# SCH_Trabalho-AP1-Subtrator_2024-10-15.net
KiCad netlist of a schematic drawn in EasyEDA
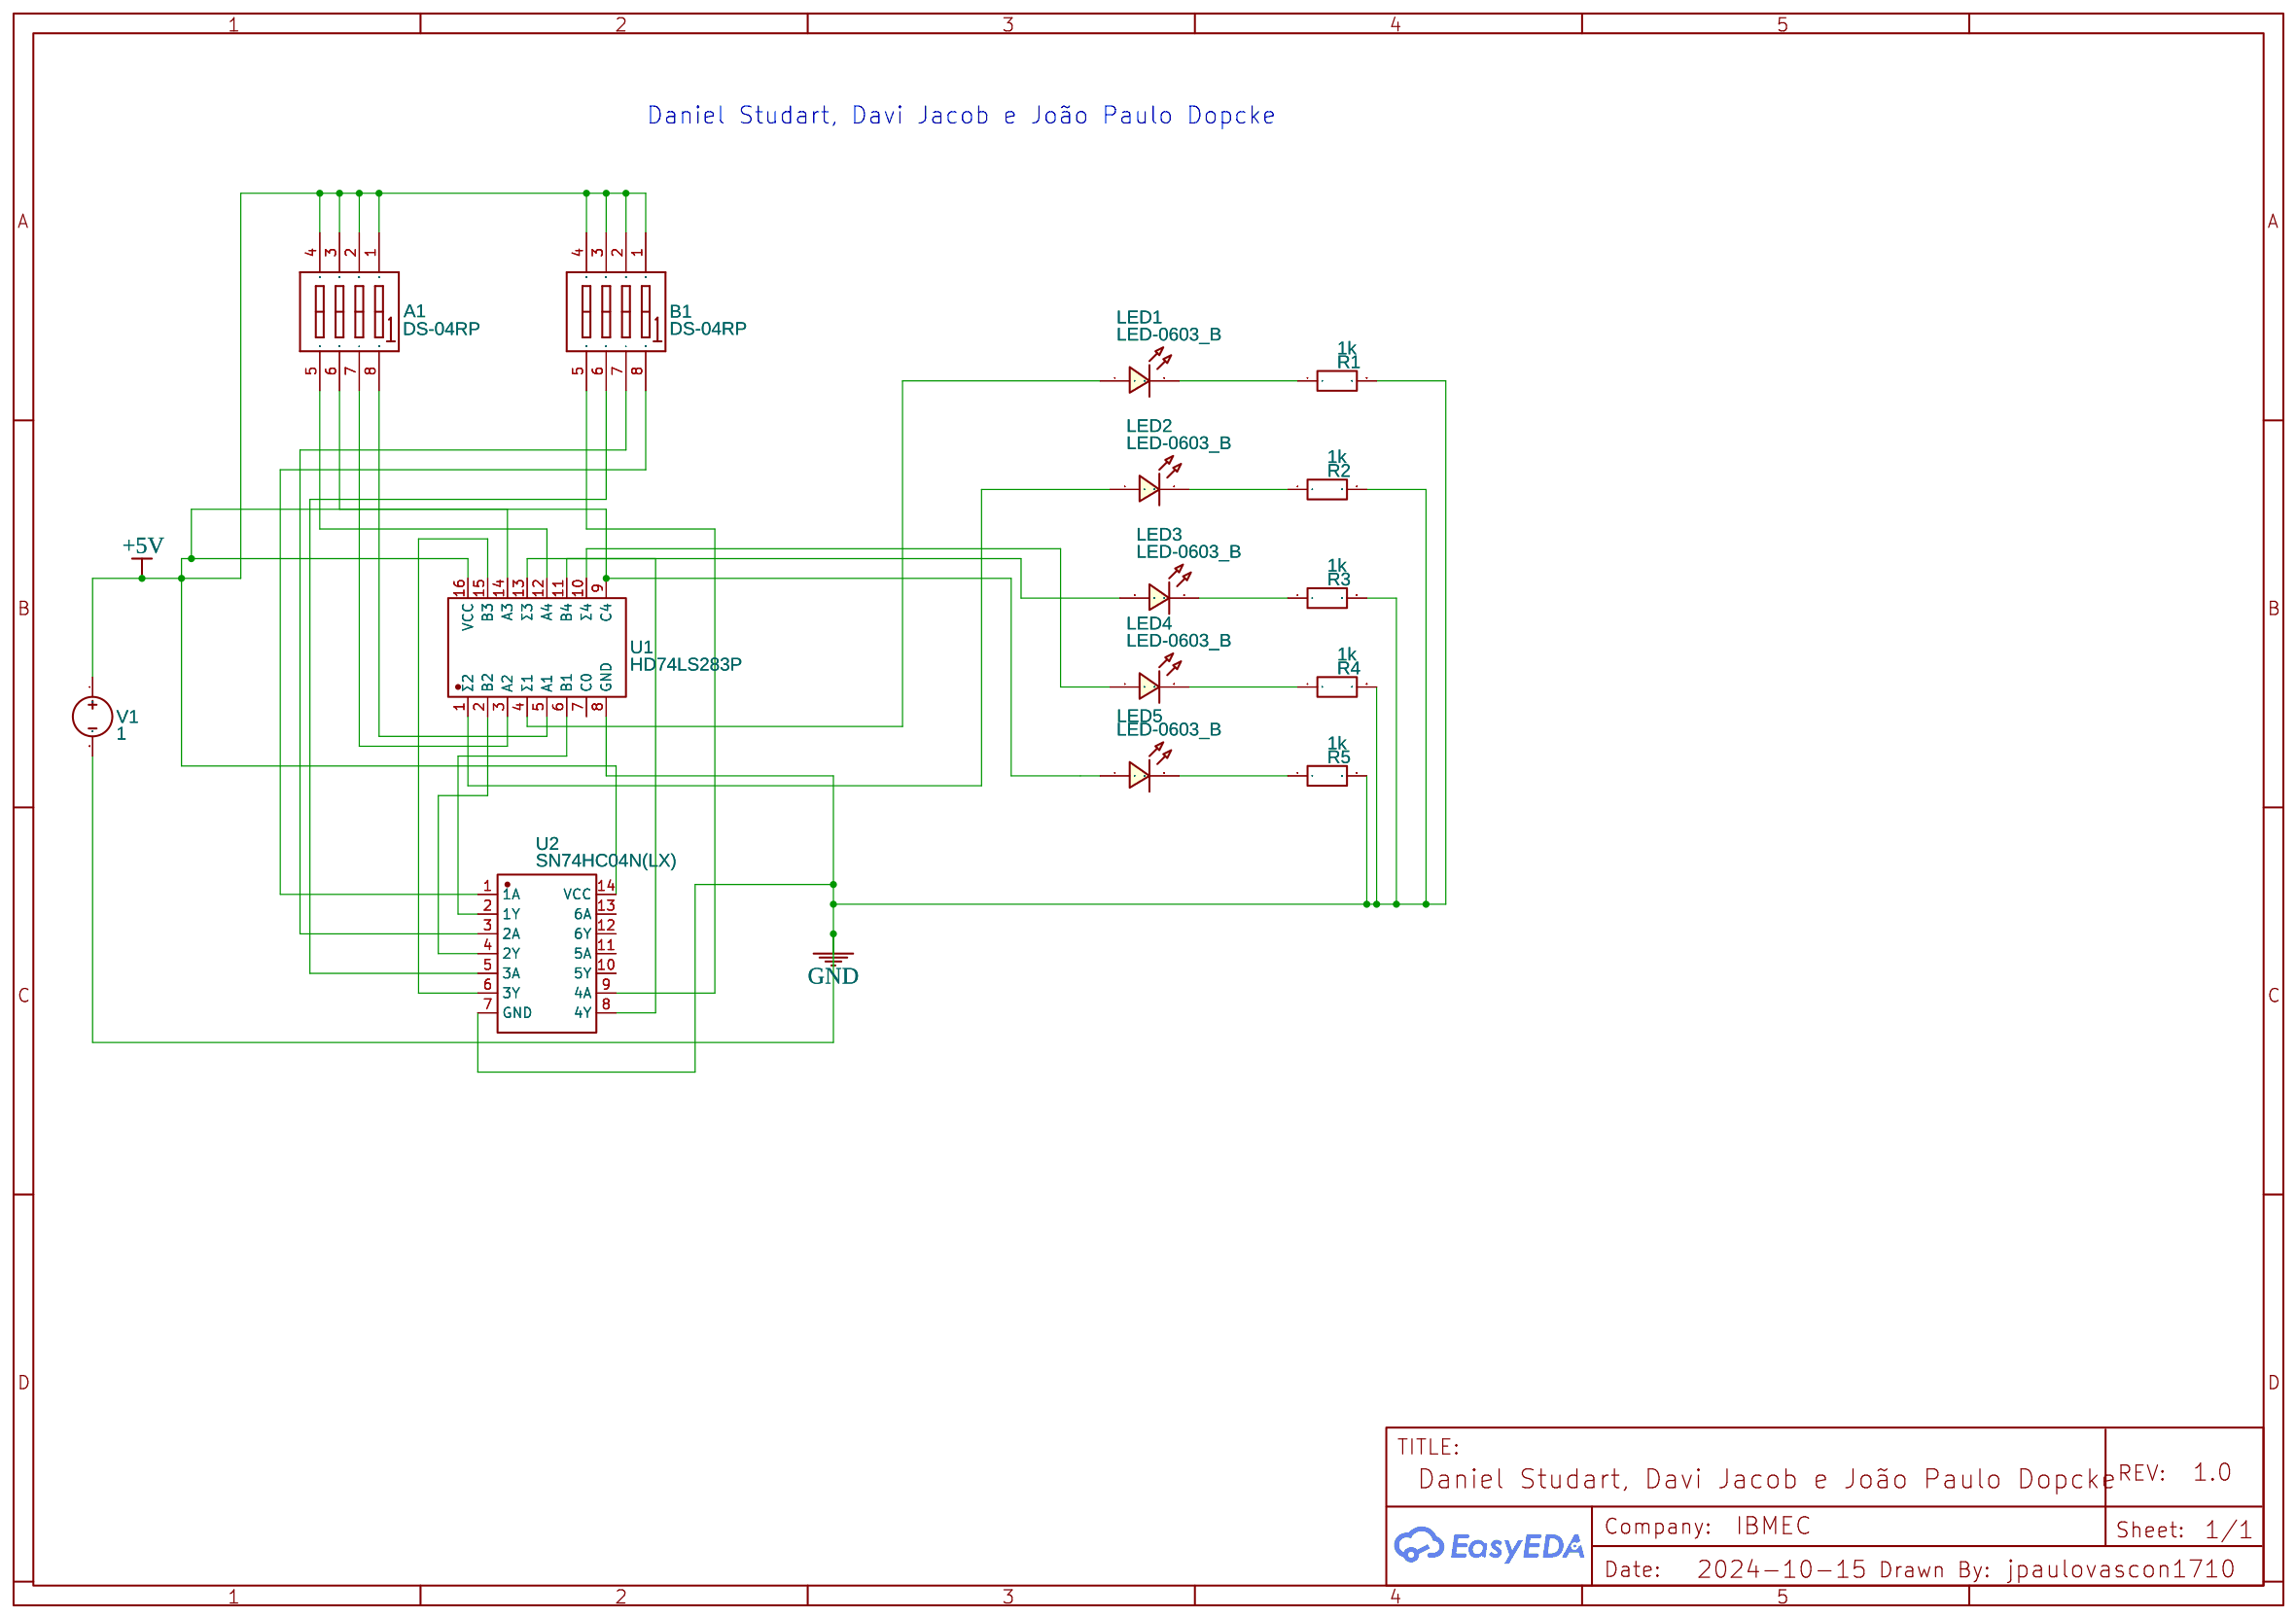
[diagram p0: schematic sheet]

(export (version "E")
  (design (tool "Eeschema 10.0.6"))
  (components
    (comp (ref "A1")
      (value "DS-04RP")
      (fields (field (name "Manufacturer") "韩国韩荣"))
      (libsource (lib "") (part "DS-04RP"))
    )
    (comp (ref "B1")
      (value "DS-04RP")
      (fields (field (name "Manufacturer") "韩国韩荣"))
      (libsource (lib "") (part "DS-04RP_1"))
    )
    (comp (ref "LED1")
      (value "LED-0603_B")
      (fields
        (field (name "Manufacturer Part") "19-217/BHC-ZL1M2RY/3T")
        (field (name "Manufacturer") "EVERLIGHT(台湾亿光)")
      )
      (libsource (lib "") (part "LED-0603_B"))
    )
    (comp (ref "LED2")
      (value "LED-0603_B")
      (fields
        (field (name "Manufacturer Part") "19-217/BHC-ZL1M2RY/3T")
        (field (name "Manufacturer") "EVERLIGHT(台湾亿光)")
      )
      (libsource (lib "") (part "LED-0603_B"))
    )
    (comp (ref "LED3")
      (value "LED-0603_B")
      (fields
        (field (name "Manufacturer Part") "19-217/BHC-ZL1M2RY/3T")
        (field (name "Manufacturer") "EVERLIGHT(台湾亿光)")
      )
      (libsource (lib "") (part "LED-0603_B"))
    )
    (comp (ref "LED4")
      (value "LED-0603_B")
      (fields
        (field (name "Manufacturer Part") "19-217/BHC-ZL1M2RY/3T")
        (field (name "Manufacturer") "EVERLIGHT(台湾亿光)")
      )
      (libsource (lib "") (part "LED-0603_B"))
    )
    (comp (ref "LED5")
      (value "LED-0603_B")
      (fields
        (field (name "Manufacturer Part") "19-217/BHC-ZL1M2RY/3T")
        (field (name "Manufacturer") "EVERLIGHT(台湾亿光)")
      )
      (libsource (lib "") (part "LED-0603_B"))
    )
    (comp (ref "R1") (value "1k") (libsource (lib "") (part "R_0603_EU")))
    (comp (ref "R2") (value "1k") (libsource (lib "") (part "R_0603_EU")))
    (comp (ref "R3") (value "1k") (libsource (lib "") (part "R_0603_EU")))
    (comp (ref "R4") (value "1k") (libsource (lib "") (part "R_0603_EU")))
    (comp (ref "R5") (value "1k") (libsource (lib "") (part "R_0603_EU")))
    (comp (ref "U1")
      (value "HD74LS283P")
      (fields (field (name "Manufacturer Part") "SN74LS283N") (field (name "Manufacturer") "TI(德州仪器)"))
      (libsource (lib "") (part "SN74LS283N"))
    )
    (comp (ref "U2")
      (value "SN74HC04N(LX)")
      (fields (field (name "Manufacturer") "LX(灵星芯微)"))
      (libsource (lib "") (part "SN74HC04N(LX)"))
    )
    (comp (ref "V1") (value "1") (libsource (lib "") (part "VDC")))
  )
  (nets
    (net (code "1") (name "+5V") (class "Default")
      (node (ref "A1") (pin "1") (pinfunction "A1_1") (pintype "input"))
      (node (ref "A1") (pin "2") (pinfunction "A2_2") (pintype "input"))
      (node (ref "A1") (pin "3") (pinfunction "A3_3") (pintype "input"))
      (node (ref "A1") (pin "4") (pinfunction "A4_4") (pintype "input"))
      (node (ref "B1") (pin "1") (pinfunction "A1_1") (pintype "input"))
      (node (ref "B1") (pin "2") (pinfunction "A2_2") (pintype "input"))
      (node (ref "B1") (pin "3") (pinfunction "A3_3") (pintype "input"))
      (node (ref "B1") (pin "4") (pinfunction "A4_4") (pintype "input"))
      (node (ref "LED5") (pin "1") (pinfunction "1_1") (pintype "unspecified"))
      (node (ref "U1") (pin "16") (pinfunction "VCC_16") (pintype "unspecified"))
      (node (ref "U1") (pin "9") (pinfunction "C4_9") (pintype "unspecified"))
      (node (ref "U2") (pin "14") (pinfunction "VCC_14") (pintype "unspecified"))
      (node (ref "V1") (pin "1") (pinfunction "1_1") (pintype "unspecified"))
    )
    (net (code "2") (name "GND") (class "Default")
      (node (ref "R1") (pin "2") (pinfunction "2_2") (pintype "unspecified"))
      (node (ref "R2") (pin "2") (pinfunction "2_2") (pintype "unspecified"))
      (node (ref "R3") (pin "2") (pinfunction "2_2") (pintype "unspecified"))
      (node (ref "R4") (pin "2") (pinfunction "2_2") (pintype "unspecified"))
      (node (ref "R5") (pin "2") (pinfunction "2_2") (pintype "unspecified"))
      (node (ref "U1") (pin "8") (pinfunction "GND_8") (pintype "unspecified"))
      (node (ref "U2") (pin "7") (pinfunction "GND_7") (pintype "unspecified"))
      (node (ref "V1") (pin "2") (pinfunction "2_2") (pintype "unspecified"))
    )
    (net (code "3") (name "Net-(LED1-Pad2)") (class "Default")
      (node (ref "LED1") (pin "2") (pinfunction "2_2") (pintype "unspecified"))
      (node (ref "R1") (pin "1") (pinfunction "1_1") (pintype "unspecified"))
    )
    (net (code "4") (name "Net-(LED2-Pad2)") (class "Default")
      (node (ref "LED2") (pin "2") (pinfunction "2_2") (pintype "unspecified"))
      (node (ref "R2") (pin "1") (pinfunction "1_1") (pintype "unspecified"))
    )
    (net (code "5") (name "Net-(LED3-Pad2)") (class "Default")
      (node (ref "LED3") (pin "2") (pinfunction "2_2") (pintype "unspecified"))
      (node (ref "R3") (pin "1") (pinfunction "1_1") (pintype "unspecified"))
    )
    (net (code "6") (name "Net-(LED4-Pad2)") (class "Default")
      (node (ref "LED4") (pin "2") (pinfunction "2_2") (pintype "unspecified"))
      (node (ref "R4") (pin "1") (pinfunction "1_1") (pintype "unspecified"))
    )
    (net (code "7") (name "Net-(LED5-Pad2)") (class "Default")
      (node (ref "LED5") (pin "2") (pinfunction "2_2") (pintype "unspecified"))
      (node (ref "R5") (pin "1") (pinfunction "1_1") (pintype "unspecified"))
    )
    (net (code "8") (name "Net-(U1-A1)") (class "Default")
      (node (ref "A1") (pin "8") (pinfunction "8_8") (pintype "input"))
      (node (ref "U1") (pin "5") (pinfunction "A1_5") (pintype "unspecified"))
    )
    (net (code "9") (name "Net-(U1-A2)") (class "Default")
      (node (ref "A1") (pin "7") (pinfunction "7_7") (pintype "input"))
      (node (ref "U1") (pin "3") (pinfunction "A2_3") (pintype "unspecified"))
    )
    (net (code "10") (name "Net-(U1-A3)") (class "Default")
      (node (ref "A1") (pin "6") (pinfunction "6_6") (pintype "input"))
      (node (ref "U1") (pin "14") (pinfunction "A3_14") (pintype "unspecified"))
    )
    (net (code "11") (name "Net-(U1-A4)") (class "Default")
      (node (ref "A1") (pin "5") (pinfunction "5_5") (pintype "input"))
      (node (ref "U1") (pin "12") (pinfunction "A4_12") (pintype "unspecified"))
    )
    (net (code "12") (name "Net-(U1-B1)") (class "Default")
      (node (ref "U1") (pin "6") (pinfunction "B1_6") (pintype "unspecified"))
      (node (ref "U2") (pin "2") (pinfunction "1Y_2") (pintype "unspecified"))
    )
    (net (code "13") (name "Net-(U1-B2)") (class "Default")
      (node (ref "U1") (pin "2") (pinfunction "B2_2") (pintype "unspecified"))
      (node (ref "U2") (pin "4") (pinfunction "2Y_4") (pintype "unspecified"))
    )
    (net (code "14") (name "Net-(U1-B3)") (class "Default")
      (node (ref "U1") (pin "15") (pinfunction "B3_15") (pintype "unspecified"))
      (node (ref "U2") (pin "6") (pinfunction "3Y_6") (pintype "unspecified"))
    )
    (net (code "15") (name "Net-(U1-B4)") (class "Default")
      (node (ref "U1") (pin "11") (pinfunction "B4_11") (pintype "unspecified"))
      (node (ref "U2") (pin "8") (pinfunction "4Y_8") (pintype "unspecified"))
    )
    (net (code "16") (name "Net-(U1-Σ1)") (class "Default")
      (node (ref "LED1") (pin "1") (pinfunction "1_1") (pintype "unspecified"))
      (node (ref "U1") (pin "4") (pinfunction "Σ1_4") (pintype "unspecified"))
    )
    (net (code "17") (name "Net-(U1-Σ2)") (class "Default")
      (node (ref "LED2") (pin "1") (pinfunction "1_1") (pintype "unspecified"))
      (node (ref "U1") (pin "1") (pinfunction "Σ2_1") (pintype "unspecified"))
    )
    (net (code "18") (name "Net-(U1-Σ3)") (class "Default")
      (node (ref "LED3") (pin "1") (pinfunction "1_1") (pintype "unspecified"))
      (node (ref "U1") (pin "13") (pinfunction "Σ3_13") (pintype "unspecified"))
    )
    (net (code "19") (name "Net-(U1-Σ4)") (class "Default")
      (node (ref "LED4") (pin "1") (pinfunction "1_1") (pintype "unspecified"))
      (node (ref "U1") (pin "10") (pinfunction "Σ4_10") (pintype "unspecified"))
    )
    (net (code "20") (name "Net-(U2-1A)") (class "Default")
      (node (ref "B1") (pin "8") (pinfunction "8_8") (pintype "input"))
      (node (ref "U2") (pin "1") (pinfunction "1A_1") (pintype "unspecified"))
    )
    (net (code "21") (name "Net-(U2-2A)") (class "Default")
      (node (ref "B1") (pin "7") (pinfunction "7_7") (pintype "input"))
      (node (ref "U2") (pin "3") (pinfunction "2A_3") (pintype "unspecified"))
    )
    (net (code "22") (name "Net-(U2-3A)") (class "Default")
      (node (ref "B1") (pin "6") (pinfunction "6_6") (pintype "input"))
      (node (ref "U2") (pin "5") (pinfunction "3A_5") (pintype "unspecified"))
    )
    (net (code "23") (name "Net-(U2-4A)") (class "Default")
      (node (ref "B1") (pin "5") (pinfunction "5_5") (pintype "input"))
      (node (ref "U2") (pin "9") (pinfunction "4A_9") (pintype "unspecified"))
    )
    (net (code "24") (name "unconnected-(U1-C0-Pad7)") (class "Default")
      (node (ref "U1") (pin "7") (pinfunction "C0_7") (pintype "unspecified"))
    )
    (net (code "25") (name "unconnected-(U2-5A-Pad11)") (class "Default")
      (node (ref "U2") (pin "11") (pinfunction "5A_11") (pintype "unspecified"))
    )
    (net (code "26") (name "unconnected-(U2-5Y-Pad10)") (class "Default")
      (node (ref "U2") (pin "10") (pinfunction "5Y_10") (pintype "unspecified"))
    )
    (net (code "27") (name "unconnected-(U2-6A-Pad13)") (class "Default")
      (node (ref "U2") (pin "13") (pinfunction "6A_13") (pintype "unspecified"))
    )
    (net (code "28") (name "unconnected-(U2-6Y-Pad12)") (class "Default")
      (node (ref "U2") (pin "12") (pinfunction "6Y_12") (pintype "unspecified"))
    )
  )
)
